# SCH_MR2-reactive-led-system-new-audio-sy.net
KiCad netlist of a schematic drawn in EasyEDA
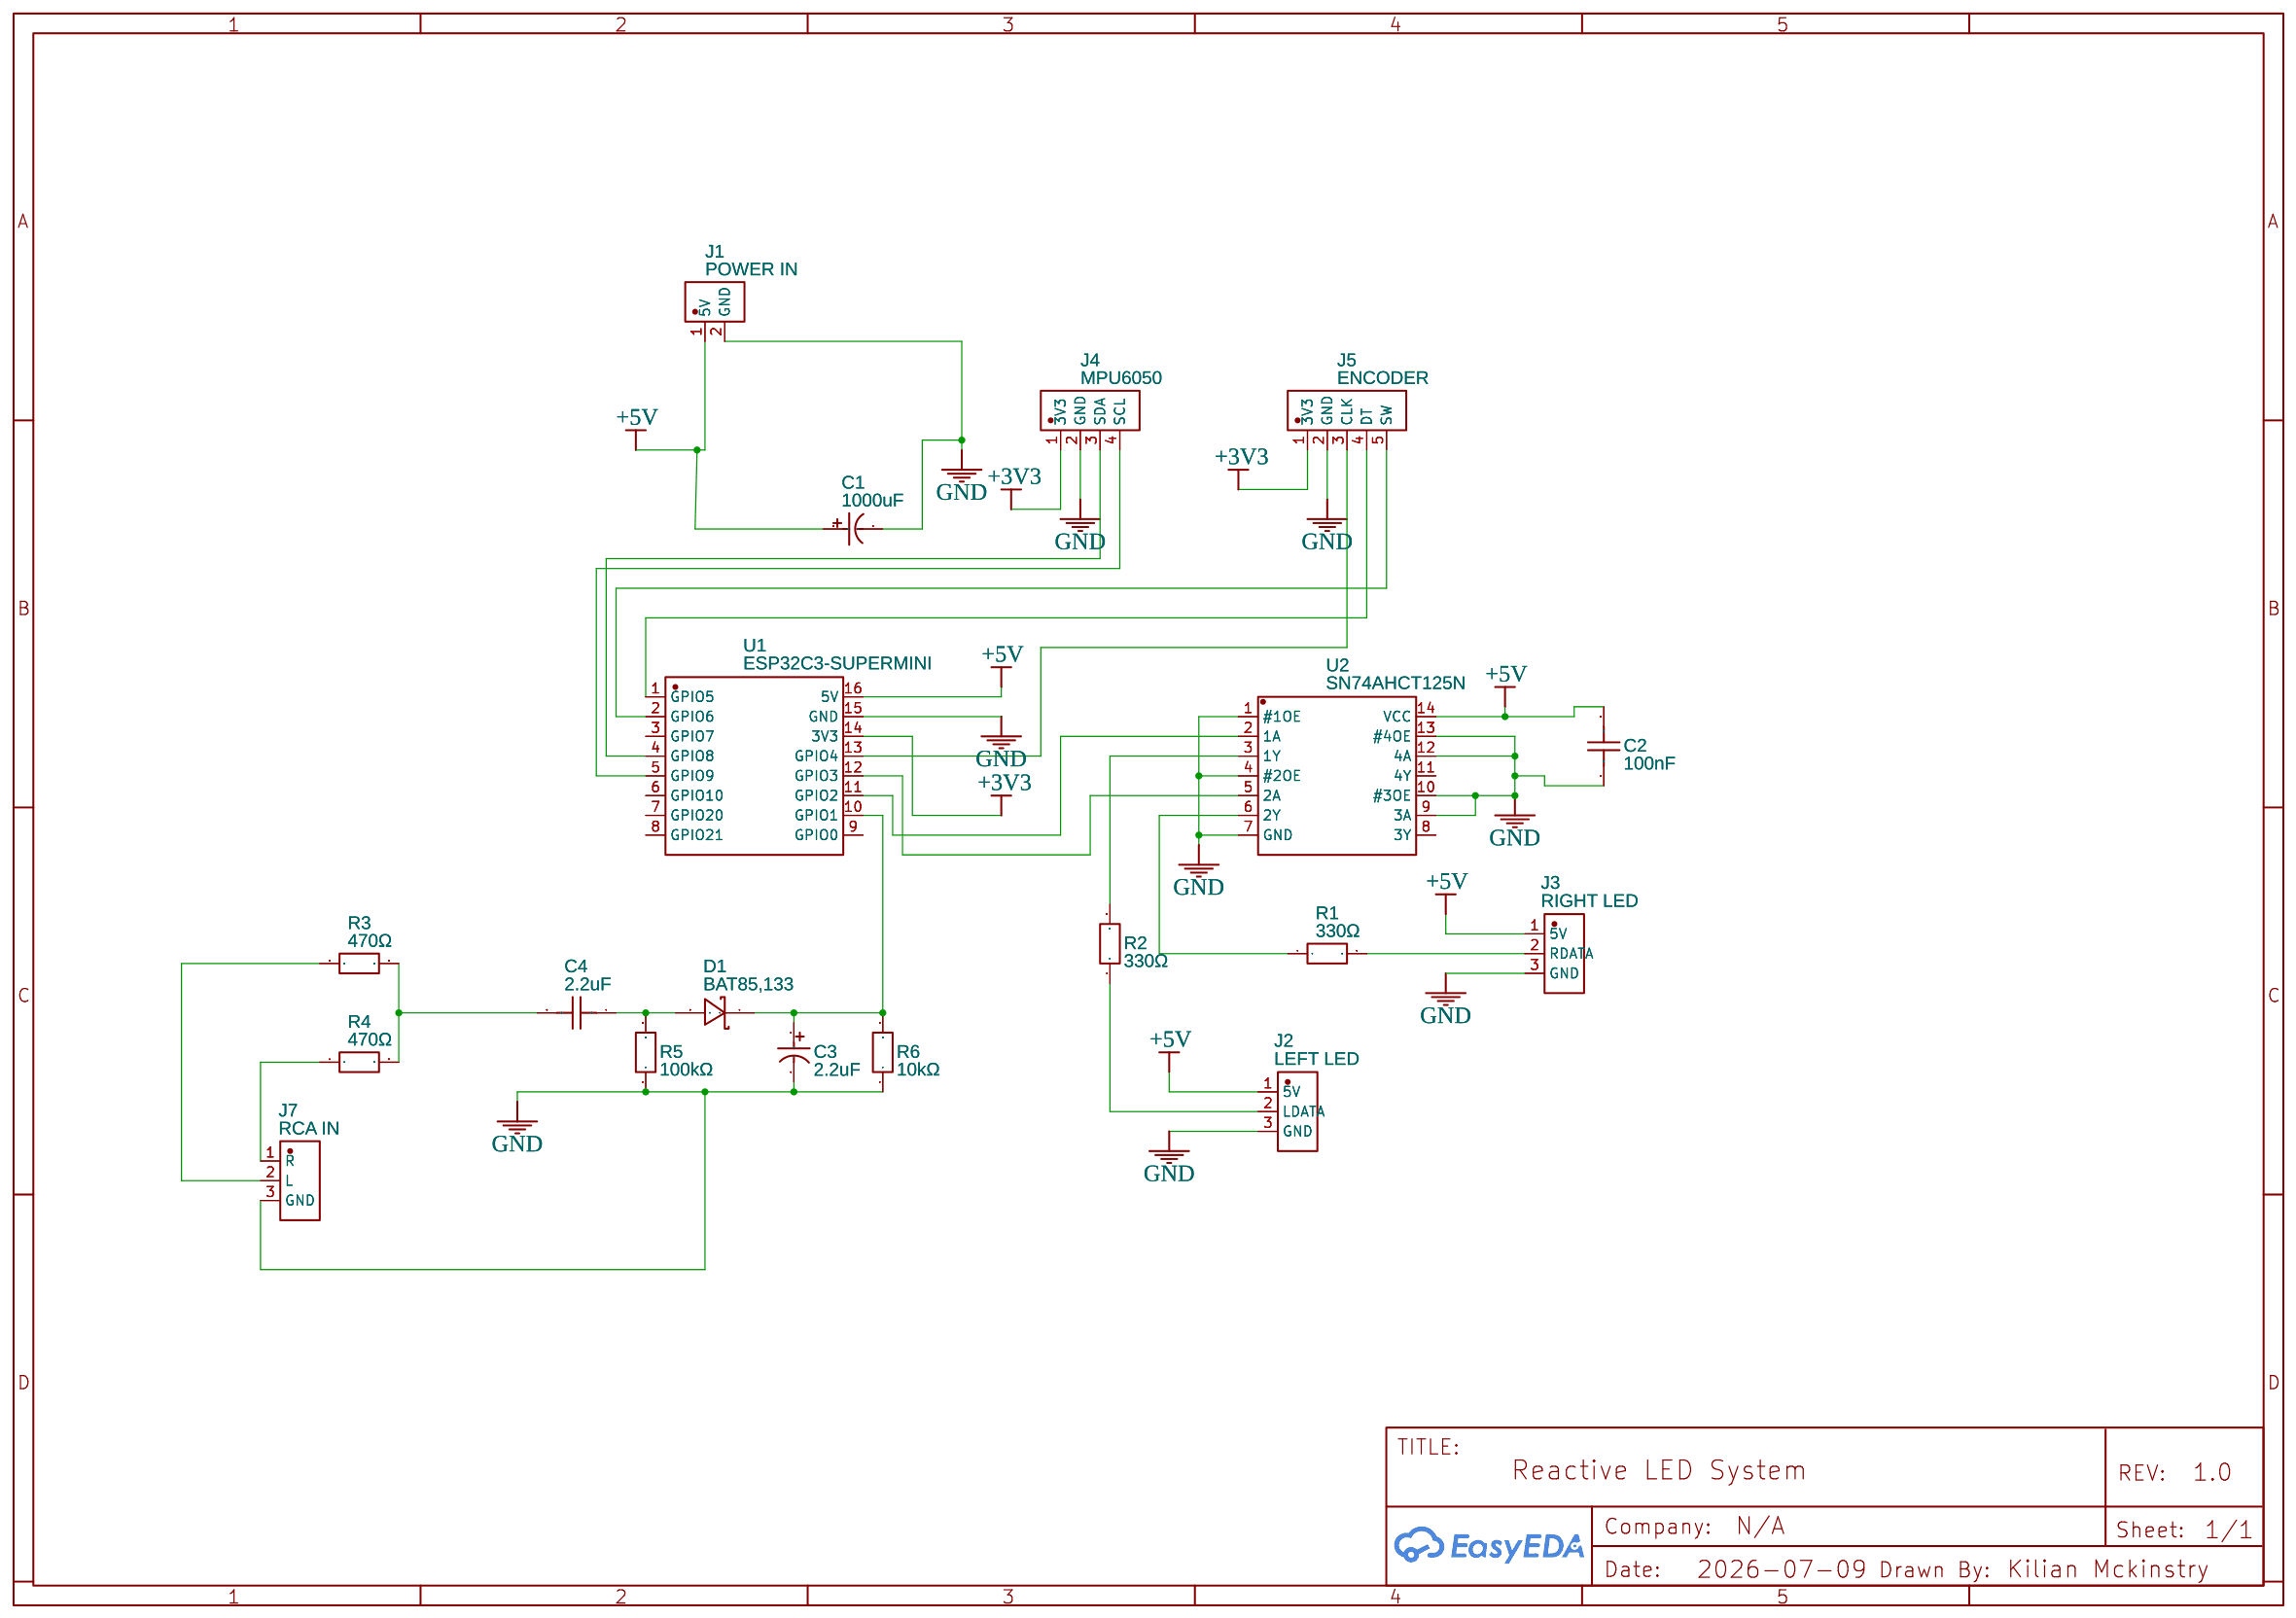
[diagram p0: schematic sheet]

(export (version "E")
  (design (tool "Eeschema 10.0.6"))
  (components
    (comp (ref "C1")
      (value "1000uF")
      (fields
        (field (name "Manufacturer Part") "KS106M050C07RR0VH2FP0")
        (field (name "Manufacturer") "Chengx(承兴)")
      )
      (libsource (lib "") (part "electrolytic capacitor10UF50V"))
    )
    (comp (ref "C2")
      (value "100nF")
      (fields
        (field (name "Manufacturer Part") "DCM472K39Y5PL6FJ5A0")
        (field (name "Manufacturer") "SHM(南方宏明)")
      )
      (libsource (lib "") (part "DCM472K39Y5PL6FJ5A0_1"))
    )
    (comp (ref "C3")
      (value "2.2uF")
      (fields
        (field (name "Manufacturer Part") "KS106M050C07RR0VH2FP0")
        (field (name "Manufacturer") "Chengx(承兴)")
      )
      (libsource (lib "") (part "electrolytic capacitor10UF50V_1"))
    )
    (comp (ref "C4")
      (value "2.2uF")
      (fields
        (field (name "Manufacturer Part") "DCM472K39Y5PL6FJ5A0")
        (field (name "Manufacturer") "SHM(南方宏明)")
      )
      (libsource (lib "") (part "DCM472K39Y5PL6FJ5A0"))
    )
    (comp (ref "D1")
      (value "BAT85,133")
      (fields (field (name "Manufacturer") "Nexperia(安世)"))
      (libsource (lib "") (part "BAT85,133"))
    )
    (comp (ref "J1")
      (value "POWER IN")
      (fields (field (name "Manufacturer Part") "XH2.54-2PIN-直针"))
      (libsource (lib "") (part "XH2.54-2PIN-直针"))
    )
    (comp (ref "J2")
      (value "LEFT LED")
      (fields (field (name "Manufacturer Part") "XH_2.54_3P"))
      (libsource (lib "") (part "XH_2.54_3P"))
    )
    (comp (ref "J3")
      (value "RIGHT LED")
      (fields (field (name "Manufacturer Part") "XH_2.54_3P"))
      (libsource (lib "") (part "XH_2.54_3P_2"))
    )
    (comp (ref "J4")
      (value "MPU6050")
      (fields (field (name "Manufacturer Part") "WAFER-XH254Z-4AL") (field (name "Manufacturer") "HANBO(汉博)"))
      (libsource (lib "") (part "WAFER-XH254Z-4AL"))
    )
    (comp (ref "J5")
      (value "ENCODER")
      (fields (field (name "Manufacturer Part") "XH_2.54_5P"))
      (libsource (lib "") (part "XH_2.54_5P"))
    )
    (comp (ref "J7")
      (value "RCA IN")
      (fields (field (name "Manufacturer Part") "XH_2.54_3P"))
      (libsource (lib "") (part "XH_2.54_3P_1"))
    )
    (comp (ref "R1")
      (value "330Ω")
      (fields (field (name "Manufacturer Part") "CR1/8W-56K±5%-ST52") (field (name "Manufacturer") "VO(翔胜)"))
      (libsource (lib "") (part "CR1/8W-56K±5%-ST52_1"))
    )
    (comp (ref "R2")
      (value "330Ω")
      (fields (field (name "Manufacturer Part") "CR1/8W-56K±5%-ST52") (field (name "Manufacturer") "VO(翔胜)"))
      (libsource (lib "") (part "CR1/8W-56K±5%-ST52"))
    )
    (comp (ref "R3")
      (value "470Ω")
      (fields (field (name "Manufacturer Part") "CR1/8W-56K±5%-ST52") (field (name "Manufacturer") "VO(翔胜)"))
      (libsource (lib "") (part "CR1/8W-56K±5%-ST52_1"))
    )
    (comp (ref "R4")
      (value "470Ω")
      (fields (field (name "Manufacturer Part") "CR1/8W-56K±5%-ST52") (field (name "Manufacturer") "VO(翔胜)"))
      (libsource (lib "") (part "CR1/8W-56K±5%-ST52_1"))
    )
    (comp (ref "R5")
      (value "100kΩ")
      (fields (field (name "Manufacturer Part") "CR1/8W-56K±5%-ST52") (field (name "Manufacturer") "VO(翔胜)"))
      (libsource (lib "") (part "CR1/8W-56K±5%-ST52"))
    )
    (comp (ref "R6")
      (value "10kΩ")
      (fields (field (name "Manufacturer Part") "CR1/8W-56K±5%-ST52") (field (name "Manufacturer") "VO(翔胜)"))
      (libsource (lib "") (part "CR1/8W-56K±5%-ST52"))
    )
    (comp (ref "U1")
      (value "ESP32C3-SUPERMINI")
      (fields (field (name "Manufacturer Part") "ESP32C3-SuperMini"))
      (libsource (lib "") (part "ESP32C3-SUPERMINI"))
    )
    (comp (ref "U2")
      (value "SN74AHCT125N")
      (fields (field (name "Manufacturer") "TI(德州仪器)"))
      (libsource (lib "") (part "SN74AHCT125N"))
    )
  )
  (nets
    (net (code "1") (name "+3V3") (class "Default")
      (node (ref "J4") (pin "1") (pinfunction "3V3_1") (pintype "unspecified"))
      (node (ref "J5") (pin "1") (pinfunction "3V3_1") (pintype "unspecified"))
      (node (ref "U1") (pin "14") (pinfunction "3V3_14") (pintype "unspecified"))
    )
    (net (code "2") (name "+5V") (class "Default")
      (node (ref "C1") (pin "1") (pinfunction "+_1") (pintype "input"))
      (node (ref "C2") (pin "2") (pinfunction "2_2") (pintype "unspecified"))
      (node (ref "J1") (pin "1") (pinfunction "5V_1") (pintype "unspecified"))
      (node (ref "J2") (pin "1") (pinfunction "5V_1") (pintype "unspecified"))
      (node (ref "J3") (pin "1") (pinfunction "5V_1") (pintype "unspecified"))
      (node (ref "U1") (pin "16") (pinfunction "5V_16") (pintype "unspecified"))
      (node (ref "U2") (pin "14") (pinfunction "VCC_14") (pintype "unspecified"))
    )
    (net (code "3") (name "GND") (class "Default")
      (node (ref "C1") (pin "2") (pinfunction "-_2") (pintype "input"))
      (node (ref "C2") (pin "1") (pinfunction "1_1") (pintype "unspecified"))
      (node (ref "C3") (pin "2") (pinfunction "-_2") (pintype "input"))
      (node (ref "J1") (pin "2") (pinfunction "GND_2") (pintype "unspecified"))
      (node (ref "J2") (pin "3") (pinfunction "GND_3") (pintype "unspecified"))
      (node (ref "J3") (pin "3") (pinfunction "GND_3") (pintype "unspecified"))
      (node (ref "J4") (pin "2") (pinfunction "GND_2") (pintype "unspecified"))
      (node (ref "J5") (pin "2") (pinfunction "GND_2") (pintype "unspecified"))
      (node (ref "J7") (pin "3") (pinfunction "GND_3") (pintype "unspecified"))
      (node (ref "R5") (pin "1") (pinfunction "1_1") (pintype "unspecified"))
      (node (ref "R6") (pin "1") (pinfunction "1_1") (pintype "unspecified"))
      (node (ref "U1") (pin "15") (pinfunction "GND_15") (pintype "unspecified"))
      (node (ref "U2") (pin "1") (pinfunction "#1OE_1") (pintype "unspecified"))
      (node (ref "U2") (pin "10") (pinfunction "#3OE_10") (pintype "unspecified"))
      (node (ref "U2") (pin "12") (pinfunction "4A_12") (pintype "unspecified"))
      (node (ref "U2") (pin "13") (pinfunction "#4OE_13") (pintype "unspecified"))
      (node (ref "U2") (pin "4") (pinfunction "#2OE_4") (pintype "unspecified"))
      (node (ref "U2") (pin "7") (pinfunction "GND_7") (pintype "unspecified"))
      (node (ref "U2") (pin "9") (pinfunction "3A_9") (pintype "unspecified"))
    )
    (net (code "4") (name "Net-(C3-+)") (class "Default")
      (node (ref "C3") (pin "1") (pinfunction "+_1") (pintype "input"))
      (node (ref "D1") (pin "1") (pinfunction "K_1") (pintype "unspecified"))
      (node (ref "R6") (pin "2") (pinfunction "2_2") (pintype "unspecified"))
      (node (ref "U1") (pin "10") (pinfunction "GPIO1_10") (pintype "unspecified"))
    )
    (net (code "5") (name "Net-(C4-Pad2)") (class "Default")
      (node (ref "C4") (pin "2") (pinfunction "2_2") (pintype "unspecified"))
      (node (ref "R3") (pin "2") (pinfunction "2_2") (pintype "unspecified"))
      (node (ref "R4") (pin "2") (pinfunction "2_2") (pintype "unspecified"))
    )
    (net (code "6") (name "Net-(D1-A)") (class "Default")
      (node (ref "C4") (pin "1") (pinfunction "1_1") (pintype "unspecified"))
      (node (ref "D1") (pin "2") (pinfunction "A_2") (pintype "unspecified"))
      (node (ref "R5") (pin "2") (pinfunction "2_2") (pintype "unspecified"))
    )
    (net (code "7") (name "Net-(J2-LDATA)") (class "Default")
      (node (ref "J2") (pin "2") (pinfunction "LDATA_2") (pintype "unspecified"))
      (node (ref "R2") (pin "1") (pinfunction "1_1") (pintype "unspecified"))
    )
    (net (code "8") (name "Net-(J3-RDATA)") (class "Default")
      (node (ref "J3") (pin "2") (pinfunction "RDATA_2") (pintype "unspecified"))
      (node (ref "R1") (pin "2") (pinfunction "2_2") (pintype "unspecified"))
    )
    (net (code "9") (name "Net-(J4-SCL)") (class "Default")
      (node (ref "J4") (pin "4") (pinfunction "SCL_4") (pintype "unspecified"))
      (node (ref "U1") (pin "5") (pinfunction "GPIO9_5") (pintype "unspecified"))
    )
    (net (code "10") (name "Net-(J4-SDA)") (class "Default")
      (node (ref "J4") (pin "3") (pinfunction "SDA_3") (pintype "unspecified"))
      (node (ref "U1") (pin "4") (pinfunction "GPIO8_4") (pintype "unspecified"))
    )
    (net (code "11") (name "Net-(J5-CLK)") (class "Default")
      (node (ref "J5") (pin "3") (pinfunction "CLK_3") (pintype "unspecified"))
      (node (ref "U1") (pin "13") (pinfunction "GPIO4_13") (pintype "unspecified"))
    )
    (net (code "12") (name "Net-(J5-DT)") (class "Default")
      (node (ref "J5") (pin "4") (pinfunction "DT_4") (pintype "unspecified"))
      (node (ref "U1") (pin "1") (pinfunction "GPIO5_1") (pintype "unspecified"))
    )
    (net (code "13") (name "Net-(J5-SW)") (class "Default")
      (node (ref "J5") (pin "5") (pinfunction "SW_5") (pintype "unspecified"))
      (node (ref "U1") (pin "2") (pinfunction "GPIO6_2") (pintype "unspecified"))
    )
    (net (code "14") (name "Net-(J7-L)") (class "Default")
      (node (ref "J7") (pin "2") (pinfunction "L_2") (pintype "unspecified"))
      (node (ref "R3") (pin "1") (pinfunction "1_1") (pintype "unspecified"))
    )
    (net (code "15") (name "Net-(J7-R)") (class "Default")
      (node (ref "J7") (pin "1") (pinfunction "R_1") (pintype "unspecified"))
      (node (ref "R4") (pin "1") (pinfunction "1_1") (pintype "unspecified"))
    )
    (net (code "16") (name "Net-(U1-GPIO2)") (class "Default")
      (node (ref "U1") (pin "11") (pinfunction "GPIO2_11") (pintype "unspecified"))
      (node (ref "U2") (pin "2") (pinfunction "1A_2") (pintype "unspecified"))
    )
    (net (code "17") (name "Net-(U1-GPIO3)") (class "Default")
      (node (ref "U1") (pin "12") (pinfunction "GPIO3_12") (pintype "unspecified"))
      (node (ref "U2") (pin "5") (pinfunction "2A_5") (pintype "unspecified"))
    )
    (net (code "18") (name "Net-(U2-1Y)") (class "Default")
      (node (ref "R2") (pin "2") (pinfunction "2_2") (pintype "unspecified"))
      (node (ref "U2") (pin "3") (pinfunction "1Y_3") (pintype "unspecified"))
    )
    (net (code "19") (name "Net-(U2-2Y)") (class "Default")
      (node (ref "R1") (pin "1") (pinfunction "1_1") (pintype "unspecified"))
      (node (ref "U2") (pin "6") (pinfunction "2Y_6") (pintype "unspecified"))
    )
    (net (code "20") (name "unconnected-(U1-GPIO0-Pad9)") (class "Default")
      (node (ref "U1") (pin "9") (pinfunction "GPIO0_9") (pintype "unspecified"))
    )
    (net (code "21") (name "unconnected-(U1-GPIO7-Pad3)") (class "Default")
      (node (ref "U1") (pin "3") (pinfunction "GPIO7_3") (pintype "unspecified"))
    )
    (net (code "22") (name "unconnected-(U1-GPIO10-Pad6)") (class "Default")
      (node (ref "U1") (pin "6") (pinfunction "GPIO10_6") (pintype "unspecified"))
    )
    (net (code "23") (name "unconnected-(U1-GPIO20-Pad7)") (class "Default")
      (node (ref "U1") (pin "7") (pinfunction "GPIO20_7") (pintype "unspecified"))
    )
    (net (code "24") (name "unconnected-(U1-GPIO21-Pad8)") (class "Default")
      (node (ref "U1") (pin "8") (pinfunction "GPIO21_8") (pintype "unspecified"))
    )
    (net (code "25") (name "unconnected-(U2-3Y-Pad8)") (class "Default")
      (node (ref "U2") (pin "8") (pinfunction "3Y_8") (pintype "unspecified"))
    )
    (net (code "26") (name "unconnected-(U2-4Y-Pad11)") (class "Default")
      (node (ref "U2") (pin "11") (pinfunction "4Y_11") (pintype "unspecified"))
    )
  )
)
